# MdA_Perifericos.net
KiCad netlist of a schematic drawn in Altium Designer
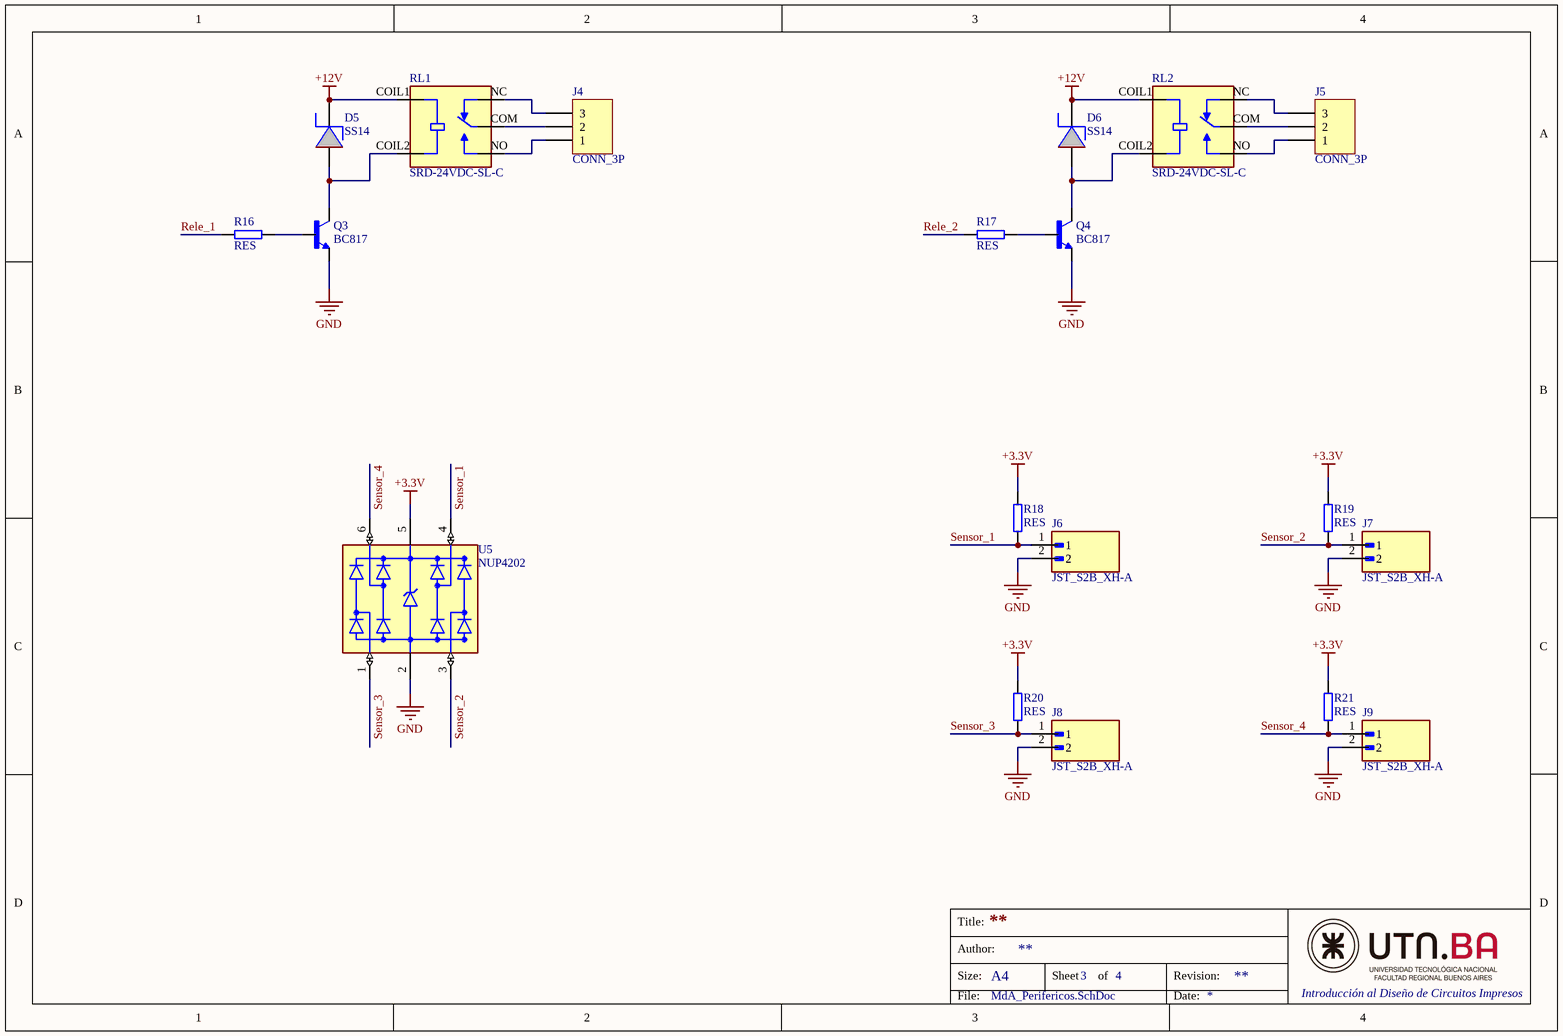
[diagram p0: MdA_Perifericos.SchDoc]

(export (version "E")
  (design (tool "Eeschema 10.0.6"))
  (components
    (comp (ref "D5")
      (value "SS14")
      (footprint "D_SMA")
      (libsource (lib "Modulo de apertura") (part "DIODE_SH"))
    )
    (comp (ref "D6")
      (value "SS14")
      (footprint "D_SMA")
      (libsource (lib "Modulo de apertura") (part "DIODE_SH"))
    )
    (comp (ref "J4")
      (value "CONN_3P")
      (footprint "BORNERA_3P_P_5mm")
      (libsource (lib "Modulo de apertura") (part "CONN_3P"))
    )
    (comp (ref "J5")
      (value "CONN_3P")
      (footprint "BORNERA_3P_P_5mm")
      (libsource (lib "Modulo de apertura") (part "CONN_3P"))
    )
    (comp (ref "J6")
      (value "JST_S2B_XH-A")
      (footprint "JST_S2B-XH-A")
      (libsource (lib "Modulo de apertura") (part "JST_S2B_XH-A"))
    )
    (comp (ref "J7")
      (value "JST_S2B_XH-A")
      (footprint "JST_S2B-XH-A")
      (libsource (lib "Modulo de apertura") (part "JST_S2B_XH-A"))
    )
    (comp (ref "J8")
      (value "JST_S2B_XH-A")
      (footprint "JST_S2B-XH-A")
      (libsource (lib "Modulo de apertura") (part "JST_S2B_XH-A"))
    )
    (comp (ref "J9")
      (value "JST_S2B_XH-A")
      (footprint "JST_S2B-XH-A")
      (libsource (lib "Modulo de apertura") (part "JST_S2B_XH-A"))
    )
    (comp (ref "Q3")
      (value "BC817")
      (footprint "SOT-23-3")
      (libsource (lib "Modulo de apertura") (part "BC817"))
    )
    (comp (ref "Q4")
      (value "BC817")
      (footprint "SOT-23-3")
      (libsource (lib "Modulo de apertura") (part "BC817"))
    )
    (comp (ref "R16") (value "RES") (footprint "R_0402") (libsource (lib "Modulo de apertura") (part "RES")))
    (comp (ref "R17") (value "RES") (footprint "R_0402") (libsource (lib "Modulo de apertura") (part "RES")))
    (comp (ref "R18") (value "RES") (footprint "R_0402") (libsource (lib "Modulo de apertura") (part "RES")))
    (comp (ref "R19") (value "RES") (footprint "R_0402") (libsource (lib "Modulo de apertura") (part "RES")))
    (comp (ref "R20") (value "RES") (footprint "R_0402") (libsource (lib "Modulo de apertura") (part "RES")))
    (comp (ref "R21") (value "RES") (footprint "R_0402") (libsource (lib "Modulo de apertura") (part "RES")))
    (comp (ref "RL1")
      (value "SRD-24VDC-SL-C")
      (footprint "RELAY_SRD-24VDC-SL-C")
      (libsource (lib "Modulo de apertura") (part "SRD-24VDC-SL-C"))
    )
    (comp (ref "RL2")
      (value "SRD-24VDC-SL-C")
      (footprint "RELAY_SRD-24VDC-SL-C")
      (libsource (lib "Modulo de apertura") (part "SRD-24VDC-SL-C"))
    )
    (comp (ref "U5")
      (value "NUP4202")
      (footprint "SOT-363")
      (libsource (lib "Modulo de apertura") (part "NUP4202"))
    )
  )
  (nets
    (net (code "1") (name "+3.3V") (class "Default")
      (node (ref "R18") (pin "1") (pinfunction "1_1") (pintype "passive"))
      (node (ref "R19") (pin "1") (pinfunction "1_1") (pintype "passive"))
      (node (ref "R20") (pin "1") (pinfunction "1_1") (pintype "passive"))
      (node (ref "R21") (pin "1") (pinfunction "1_1") (pintype "passive"))
      (node (ref "U5") (pin "5") (pinfunction "VDD_5") (pintype "power_in"))
    )
    (net (code "2") (name "+12V") (class "Default")
      (node (ref "D5") (pin "2") (pinfunction "K_2") (pintype "passive"))
      (node (ref "D6") (pin "2") (pinfunction "K_2") (pintype "passive"))
      (node (ref "RL1") (pin "COIL1") (pinfunction "COIL1_COIL1") (pintype "passive"))
      (node (ref "RL2") (pin "COIL1") (pinfunction "COIL1_COIL1") (pintype "passive"))
    )
    (net (code "3") (name "/Rele_1") (class "Default")
      (node (ref "R16") (pin "1") (pinfunction "1_1") (pintype "passive"))
    )
    (net (code "4") (name "/Rele_2") (class "Default")
      (node (ref "R17") (pin "1") (pinfunction "1_1") (pintype "passive"))
    )
    (net (code "5") (name "/Sensor_1") (class "Default")
      (node (ref "J6") (pin "1") (pinfunction "1_1") (pintype "passive"))
      (node (ref "R18") (pin "2") (pinfunction "2_2") (pintype "passive"))
      (node (ref "U5") (pin "4") (pinfunction "IO3_4") (pintype "bidirectional"))
    )
    (net (code "6") (name "/Sensor_2") (class "Default")
      (node (ref "J7") (pin "1") (pinfunction "1_1") (pintype "passive"))
      (node (ref "R19") (pin "2") (pinfunction "2_2") (pintype "passive"))
      (node (ref "U5") (pin "3") (pinfunction "IO2_3") (pintype "bidirectional"))
    )
    (net (code "7") (name "/Sensor_3") (class "Default")
      (node (ref "J8") (pin "1") (pinfunction "1_1") (pintype "passive"))
      (node (ref "R20") (pin "2") (pinfunction "2_2") (pintype "passive"))
      (node (ref "U5") (pin "1") (pinfunction "IO1_1") (pintype "bidirectional"))
    )
    (net (code "8") (name "/Sensor_4") (class "Default")
      (node (ref "J9") (pin "1") (pinfunction "1_1") (pintype "passive"))
      (node (ref "R21") (pin "2") (pinfunction "2_2") (pintype "passive"))
      (node (ref "U5") (pin "6") (pinfunction "IO4_6") (pintype "bidirectional"))
    )
    (net (code "9") (name "GND") (class "Default")
      (node (ref "J6") (pin "2") (pinfunction "2_2") (pintype "passive"))
      (node (ref "J7") (pin "2") (pinfunction "2_2") (pintype "passive"))
      (node (ref "J8") (pin "2") (pinfunction "2_2") (pintype "passive"))
      (node (ref "J9") (pin "2") (pinfunction "2_2") (pintype "passive"))
      (node (ref "Q3") (pin "2") (pinfunction "E_2") (pintype "passive"))
      (node (ref "Q4") (pin "2") (pinfunction "E_2") (pintype "passive"))
      (node (ref "U5") (pin "2") (pinfunction "GND_2") (pintype "power_in"))
    )
    (net (code "10") (name "Net-(D5-A)") (class "Default")
      (node (ref "D5") (pin "1") (pinfunction "A_1") (pintype "passive"))
      (node (ref "Q3") (pin "3") (pinfunction "C_3") (pintype "passive"))
      (node (ref "RL1") (pin "COIL2") (pinfunction "COIL2_COIL2") (pintype "passive"))
    )
    (net (code "11") (name "Net-(D6-A)") (class "Default")
      (node (ref "D6") (pin "1") (pinfunction "A_1") (pintype "passive"))
      (node (ref "Q4") (pin "3") (pinfunction "C_3") (pintype "passive"))
      (node (ref "RL2") (pin "COIL2") (pinfunction "COIL2_COIL2") (pintype "passive"))
    )
    (net (code "12") (name "Net-(J4-Pad1)") (class "Default")
      (node (ref "J4") (pin "1") (pinfunction "1_1") (pintype "passive"))
      (node (ref "RL1") (pin "NO") (pinfunction "NO_NO") (pintype "passive"))
    )
    (net (code "13") (name "Net-(J4-Pad2)") (class "Default")
      (node (ref "J4") (pin "2") (pinfunction "2_2") (pintype "passive"))
      (node (ref "RL1") (pin "COM") (pinfunction "COM_COM") (pintype "passive"))
    )
    (net (code "14") (name "Net-(J4-Pad3)") (class "Default")
      (node (ref "J4") (pin "3") (pinfunction "3_3") (pintype "passive"))
      (node (ref "RL1") (pin "NC") (pinfunction "NC_NC") (pintype "passive"))
    )
    (net (code "15") (name "Net-(J5-Pad1)") (class "Default")
      (node (ref "J5") (pin "1") (pinfunction "1_1") (pintype "passive"))
      (node (ref "RL2") (pin "NO") (pinfunction "NO_NO") (pintype "passive"))
    )
    (net (code "16") (name "Net-(J5-Pad2)") (class "Default")
      (node (ref "J5") (pin "2") (pinfunction "2_2") (pintype "passive"))
      (node (ref "RL2") (pin "COM") (pinfunction "COM_COM") (pintype "passive"))
    )
    (net (code "17") (name "Net-(J5-Pad3)") (class "Default")
      (node (ref "J5") (pin "3") (pinfunction "3_3") (pintype "passive"))
      (node (ref "RL2") (pin "NC") (pinfunction "NC_NC") (pintype "passive"))
    )
    (net (code "18") (name "Net-(Q3-B)") (class "Default")
      (node (ref "Q3") (pin "1") (pinfunction "B_1") (pintype "passive"))
      (node (ref "R16") (pin "2") (pinfunction "2_2") (pintype "passive"))
    )
    (net (code "19") (name "Net-(Q4-B)") (class "Default")
      (node (ref "Q4") (pin "1") (pinfunction "B_1") (pintype "passive"))
      (node (ref "R17") (pin "2") (pinfunction "2_2") (pintype "passive"))
    )
  )
)
